# leo_joy_gamer_v2.net
KiCad netlist of a schematic drawn in EAGLE
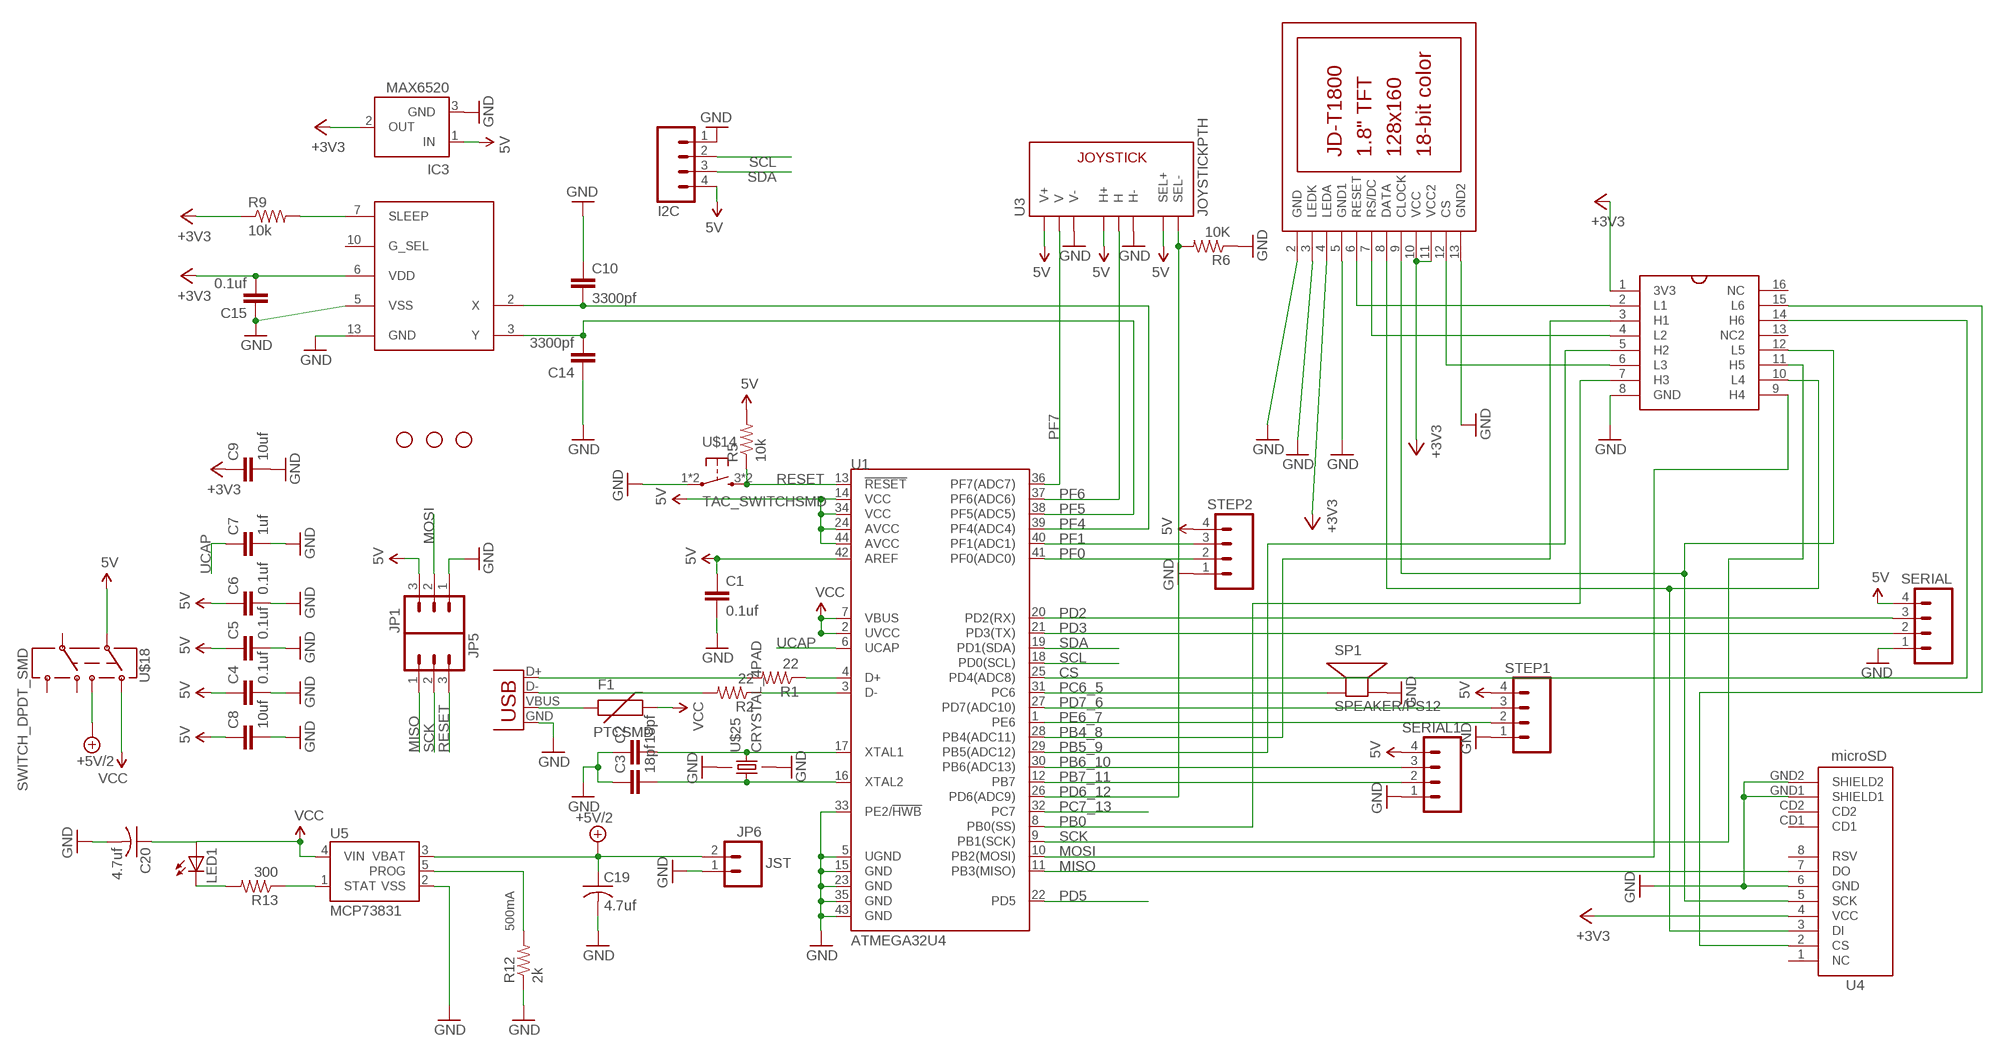
[diagram p0: schematic, sheet 1]

(export (version "E")
  (design (tool "Eeschema 10.0.6"))
  (components
    (comp (ref "C1")
      (value "0.1uf")
      (footprint "eagle-import:0805")
      (libsource (lib "eagle-import") (part "CAP0805"))
    )
    (comp (ref "C2")
      (value "18pf")
      (footprint "eagle-import:0805")
      (libsource (lib "eagle-import") (part "CAP0805"))
    )
    (comp (ref "C3")
      (value "18pf")
      (footprint "eagle-import:0805")
      (libsource (lib "eagle-import") (part "CAP0805"))
    )
    (comp (ref "C4")
      (value "0.1uf")
      (footprint "eagle-import:0805")
      (libsource (lib "eagle-import") (part "CAP0805"))
    )
    (comp (ref "C5")
      (value "0.1uf")
      (footprint "eagle-import:0805")
      (libsource (lib "eagle-import") (part "CAP0805"))
    )
    (comp (ref "C6")
      (value "0.1uf")
      (footprint "eagle-import:0805")
      (libsource (lib "eagle-import") (part "CAP0805"))
    )
    (comp (ref "C7")
      (value "1uf")
      (footprint "eagle-import:0805")
      (libsource (lib "eagle-import") (part "CAP0805"))
    )
    (comp (ref "C8")
      (value "10uf")
      (footprint "eagle-import:0805")
      (libsource (lib "eagle-import") (part "CAP0805"))
    )
    (comp (ref "C9")
      (value "10uf")
      (footprint "eagle-import:0805")
      (libsource (lib "eagle-import") (part "CAP0805"))
    )
    (comp (ref "C10")
      (value "3300pf")
      (footprint "eagle-import:0805")
      (libsource (lib "eagle-import") (part "CAP0805"))
    )
    (comp (ref "C14")
      (value "3300pf")
      (footprint "eagle-import:0805")
      (libsource (lib "eagle-import") (part "CAP0805"))
    )
    (comp (ref "C15")
      (value "0.1uf")
      (footprint "eagle-import:0805")
      (libsource (lib "eagle-import") (part "CAP0805"))
    )
    (comp (ref "C19")
      (value "4.7uf")
      (footprint "eagle-import:C0603")
      (libsource (lib "eagle-import") (part "C-USC0603"))
    )
    (comp (ref "C20")
      (value "4.7uf")
      (footprint "eagle-import:C0603")
      (libsource (lib "eagle-import") (part "C-USC0603"))
    )
    (comp (ref "F1")
      (value "PTCSMD")
      (footprint "eagle-import:PTC-1206")
      (libsource (lib "eagle-import") (part "PTCSMD"))
    )
    (comp (ref "I2C")
      (value "M04LOCK")
      (footprint "eagle-import:1X04_LOCK")
      (libsource (lib "eagle-import") (part "M04LOCK"))
    )
    (comp (ref "IC3")
      (value "MAX6520")
      (footprint "eagle-import:SOT23")
      (libsource (lib "eagle-import") (part "MAX6520"))
    )
    (comp (ref "JP1")
      (value "M03LOCK")
      (footprint "eagle-import:1X03_LOCK")
      (libsource (lib "eagle-import") (part "M03LOCK"))
    )
    (comp (ref "JP2")
      (value "STAND-OFF")
      (footprint "eagle-import:STAND-OFF")
      (libsource (lib "eagle-import") (part "STAND-OFF"))
    )
    (comp (ref "JP3")
      (value "STAND-OFF")
      (footprint "eagle-import:STAND-OFF")
      (libsource (lib "eagle-import") (part "STAND-OFF"))
    )
    (comp (ref "JP4")
      (value "STAND-OFF")
      (footprint "eagle-import:STAND-OFF")
      (libsource (lib "eagle-import") (part "STAND-OFF"))
    )
    (comp (ref "JP5")
      (value "M03LOCK")
      (footprint "eagle-import:1X03_LOCK")
      (libsource (lib "eagle-import") (part "M03LOCK"))
    )
    (comp (ref "JP6")
      (value "JST")
      (footprint "eagle-import:JST-2-PTH")
      (libsource (lib "eagle-import") (part "M02JST-PTH-2"))
    )
    (comp (ref "LCD1")
      (value "JD-T1800")
      (footprint "eagle-import:JD-T1800")
      (libsource (lib "eagle-import") (part "JD-T1800"))
    )
    (comp (ref "LED1")
      (value "LEDCHIPLED_1206")
      (footprint "eagle-import:CHIPLED_1206")
      (libsource (lib "eagle-import") (part "LEDCHIPLED_1206"))
    )
    (comp (ref "R1")
      (value "22")
      (footprint "eagle-import:M0805")
      (libsource (lib "eagle-import") (part "R-US_M0805"))
    )
    (comp (ref "R2")
      (value "22")
      (footprint "eagle-import:M0805")
      (libsource (lib "eagle-import") (part "R-US_M0805"))
    )
    (comp (ref "R5")
      (value "10k")
      (footprint "eagle-import:M0805")
      (libsource (lib "eagle-import") (part "R-US_M0805"))
    )
    (comp (ref "R6")
      (value "10K")
      (footprint "eagle-import:R0603")
      (libsource (lib "eagle-import") (part "R-US_R0603"))
    )
    (comp (ref "R9")
      (value "10k")
      (footprint "eagle-import:R0805")
      (libsource (lib "eagle-import") (part "R-US_R0805"))
    )
    (comp (ref "R12")
      (value "2k")
      (footprint "eagle-import:R0805")
      (libsource (lib "eagle-import") (part "R-US_R0805"))
    )
    (comp (ref "R13")
      (value "300")
      (footprint "eagle-import:R0805")
      (libsource (lib "eagle-import") (part "R-US_R0805"))
    )
    (comp (ref "SERIAL")
      (value "M04LOCK")
      (footprint "eagle-import:1X04_LOCK")
      (libsource (lib "eagle-import") (part "M04LOCK"))
    )
    (comp (ref "SERIAL1")
      (value "M04LOCK")
      (footprint "eagle-import:1X04_LOCK")
      (libsource (lib "eagle-import") (part "M04LOCK"))
    )
    (comp (ref "SP1")
      (value "SPEAKER/PS12")
      (footprint "eagle-import:PS12")
      (libsource (lib "eagle-import") (part "SPEAKER/PS12"))
    )
    (comp (ref "STEP1")
      (value "M04LOCK")
      (footprint "eagle-import:1X04_LOCK")
      (libsource (lib "eagle-import") (part "M04LOCK"))
    )
    (comp (ref "STEP2")
      (value "M04LOCK")
      (footprint "eagle-import:1X04_LOCK")
      (libsource (lib "eagle-import") (part "M04LOCK"))
    )
    (comp (ref "U$2")
      (value "CD4050SO_16_MIDDLE")
      (footprint "eagle-import:SO_16")
      (libsource (lib "eagle-import") (part "CD4050SO_16_MIDDLE"))
    )
    (comp (ref "U$12")
      (value "ACCELEROMETER_MMA6331L")
      (footprint "eagle-import:LGA14")
      (libsource (lib "eagle-import") (part "ACCELEROMETER_MMA6331L"))
    )
    (comp (ref "U$14")
      (value "TAC_SWITCHSMD")
      (footprint "eagle-import:TAC_SWITCH_SMD")
      (libsource (lib "eagle-import") (part "TAC_SWITCHSMD"))
    )
    (comp (ref "U$18")
      (value "SWITCH_DPDT_SMD")
      (footprint "eagle-import:SWITCH_DPDT")
      (libsource (lib "eagle-import") (part "SWITCH_DPDT_SMD"))
    )
    (comp (ref "U$25")
      (value "CRYSTAL_4PAD")
      (footprint "eagle-import:CRYSTAL_4PAD_TINY")
      (libsource (lib "eagle-import") (part "CRYSTAL_4PAD"))
    )
    (comp (ref "U1")
      (value "ATMEGA32U4")
      (footprint "eagle-import:QFN-44-NOPAD")
      (libsource (lib "eagle-import") (part "ATMEGA32U4QFN2"))
    )
    (comp (ref "U3")
      (value "JOYSTICKPTH")
      (footprint "eagle-import:JOYSTICK")
      (libsource (lib "eagle-import") (part "JOYSTICKPTH"))
    )
    (comp (ref "U4")
      (value "microSD")
      (footprint "eagle-import:MICRO-SD-SOCKET-PP")
      (libsource (lib "eagle-import") (part "USD-SOCKETSMD"))
    )
    (comp (ref "U5")
      (value "MCP73831")
      (footprint "eagle-import:SOT23-5")
      (libsource (lib "eagle-import") (part "MCP73831"))
    )
    (comp (ref "X1")
      (value "USBSMD")
      (footprint "eagle-import:USB-MINIB")
      (libsource (lib "eagle-import") (part "USBSMD"))
    )
  )
  (nets
    (net (code "1") (name "+3V3") (class "Default")
      (node (ref "C15") (pin "2") (pinfunction "2_2") (pintype "passive"))
      (node (ref "C9") (pin "1") (pinfunction "1_1") (pintype "passive"))
      (node (ref "IC3") (pin "2") (pinfunction "OUT_2") (pintype "input"))
      (node (ref "LCD1") (pin "10") (pinfunction "VCC_10") (pintype "power_in"))
      (node (ref "LCD1") (pin "11") (pinfunction "VCC2_11") (pintype "power_in"))
      (node (ref "LCD1") (pin "4") (pinfunction "LEDA_4") (pintype "input"))
      (node (ref "R9") (pin "1") (pinfunction "1_1") (pintype "passive"))
      (node (ref "U$12") (pin "6") (pinfunction "VDD_6") (pintype "bidirectional"))
      (node (ref "U$2") (pin "1") (pinfunction "3V3_1") (pintype "bidirectional"))
      (node (ref "U4") (pin "4") (pinfunction "VCC_4") (pintype "bidirectional"))
    )
    (net (code "2") (name "+5V{slash}2") (class "Default")
      (node (ref "C19") (pin "1") (pinfunction "1_1") (pintype "passive"))
      (node (ref "JP6") (pin "2") (pinfunction "2_2") (pintype "passive"))
      (node (ref "U$18") (pin "8") (pinfunction "3_8") (pintype "bidirectional"))
      (node (ref "U5") (pin "3") (pinfunction "VBAT_3") (pintype "power_in"))
    )
    (net (code "3") (name "/CS") (class "Default")
      (node (ref "U$2") (pin "14") (pinfunction "H6_14") (pintype "bidirectional"))
      (node (ref "U1") (pin "25") (pinfunction "PD4(ADC8)_25") (pintype "bidirectional"))
    )
    (net (code "4") (name "/MISO") (class "Default")
      (node (ref "JP5") (pin "1") (pinfunction "1_1") (pintype "passive"))
      (node (ref "U1") (pin "11") (pinfunction "PB3(MISO)_11") (pintype "bidirectional"))
      (node (ref "U4") (pin "7") (pinfunction "DO_7") (pintype "bidirectional"))
    )
    (net (code "5") (name "/MOSI") (class "Default")
      (node (ref "JP1") (pin "2") (pinfunction "2_2") (pintype "passive"))
      (node (ref "U$2") (pin "9") (pinfunction "H4_9") (pintype "bidirectional"))
      (node (ref "U1") (pin "10") (pinfunction "PB2(MOSI)_10") (pintype "bidirectional"))
    )
    (net (code "6") (name "/PB0") (class "Default")
      (node (ref "U$2") (pin "7") (pinfunction "H3_7") (pintype "bidirectional"))
      (node (ref "U1") (pin "8") (pinfunction "PB0(SS)_8") (pintype "bidirectional"))
    )
    (net (code "7") (name "/PB4_8") (class "Default")
      (node (ref "U$2") (pin "3") (pinfunction "H1_3") (pintype "bidirectional"))
      (node (ref "U1") (pin "28") (pinfunction "PB4(ADC11)_28") (pintype "bidirectional"))
    )
    (net (code "8") (name "/PB5_9") (class "Default")
      (node (ref "U$2") (pin "5") (pinfunction "H2_5") (pintype "bidirectional"))
      (node (ref "U1") (pin "29") (pinfunction "PB5(ADC12)_29") (pintype "bidirectional"))
    )
    (net (code "9") (name "/PB6_10") (class "Default")
      (node (ref "SERIAL1") (pin "3") (pinfunction "3_3") (pintype "passive"))
      (node (ref "U1") (pin "30") (pinfunction "PB6(ADC13)_30") (pintype "bidirectional"))
    )
    (net (code "10") (name "/PB7_11") (class "Default")
      (node (ref "SERIAL1") (pin "2") (pinfunction "2_2") (pintype "passive"))
      (node (ref "U1") (pin "12") (pinfunction "PB7_12") (pintype "bidirectional"))
    )
    (net (code "11") (name "/PC6_5") (class "Default")
      (node (ref "SP1") (pin "P$1") (pinfunction "+_P$1") (pintype "passive"))
      (node (ref "U1") (pin "31") (pinfunction "PC6_31") (pintype "bidirectional"))
    )
    (net (code "12") (name "/PC7_13") (class "Default")
      (node (ref "U1") (pin "32") (pinfunction "PC7_32") (pintype "bidirectional"))
    )
    (net (code "13") (name "/PD2") (class "Default")
      (node (ref "SERIAL") (pin "3") (pinfunction "3_3") (pintype "passive"))
      (node (ref "U1") (pin "20") (pinfunction "PD2(RX)_20") (pintype "bidirectional"))
    )
    (net (code "14") (name "/PD3") (class "Default")
      (node (ref "SERIAL") (pin "2") (pinfunction "2_2") (pintype "passive"))
      (node (ref "U1") (pin "21") (pinfunction "PD3(TX)_21") (pintype "bidirectional"))
    )
    (net (code "15") (name "/PD5") (class "Default")
      (node (ref "U1") (pin "22") (pinfunction "PD5_22") (pintype "bidirectional"))
    )
    (net (code "16") (name "/PD6_12") (class "Default")
      (node (ref "R6") (pin "2") (pinfunction "2_2") (pintype "passive"))
      (node (ref "U1") (pin "26") (pinfunction "PD6(ADC9)_26") (pintype "bidirectional"))
      (node (ref "U3") (pin "B2A") (pinfunction "SEL-_B2A") (pintype "bidirectional"))
    )
    (net (code "17") (name "/PD7_6") (class "Default")
      (node (ref "STEP1") (pin "3") (pinfunction "3_3") (pintype "passive"))
      (node (ref "U1") (pin "27") (pinfunction "PD7(ADC10)_27") (pintype "bidirectional"))
    )
    (net (code "18") (name "/PE6_7") (class "Default")
      (node (ref "STEP1") (pin "2") (pinfunction "2_2") (pintype "passive"))
      (node (ref "U1") (pin "1") (pinfunction "PE6_1") (pintype "bidirectional"))
    )
    (net (code "19") (name "/PF0") (class "Default")
      (node (ref "STEP2") (pin "2") (pinfunction "2_2") (pintype "passive"))
      (node (ref "U1") (pin "41") (pinfunction "PF0(ADC0)_41") (pintype "bidirectional"))
    )
    (net (code "20") (name "/PF1") (class "Default")
      (node (ref "STEP2") (pin "3") (pinfunction "3_3") (pintype "passive"))
      (node (ref "U1") (pin "40") (pinfunction "PF1(ADC1)_40") (pintype "bidirectional"))
    )
    (net (code "21") (name "/PF4") (class "Default")
      (node (ref "C10") (pin "2") (pinfunction "2_2") (pintype "passive"))
      (node (ref "U$12") (pin "2") (pinfunction "X_2") (pintype "bidirectional"))
      (node (ref "U1") (pin "39") (pinfunction "PF4(ADC4)_39") (pintype "bidirectional"))
    )
    (net (code "22") (name "/PF5") (class "Default")
      (node (ref "C14") (pin "2") (pinfunction "2_2") (pintype "passive"))
      (node (ref "U$12") (pin "3") (pinfunction "Y_3") (pintype "bidirectional"))
      (node (ref "U1") (pin "38") (pinfunction "PF5(ADC5)_38") (pintype "bidirectional"))
    )
    (net (code "23") (name "/PF6") (class "Default")
      (node (ref "U1") (pin "37") (pinfunction "PF6(ADC6)_37") (pintype "bidirectional"))
      (node (ref "U3") (pin "H2") (pinfunction "H_H2") (pintype "bidirectional"))
    )
    (net (code "24") (name "/PF7") (class "Default")
      (node (ref "U1") (pin "36") (pinfunction "PF7(ADC7)_36") (pintype "bidirectional"))
      (node (ref "U3") (pin "V2") (pinfunction "V_V2") (pintype "bidirectional"))
    )
    (net (code "25") (name "/RESET") (class "Default")
      (node (ref "JP5") (pin "3") (pinfunction "3_3") (pintype "passive"))
      (node (ref "R5") (pin "1") (pinfunction "1_1") (pintype "passive"))
      (node (ref "U$14") (pin "3") (pinfunction "3_3") (pintype "passive"))
      (node (ref "U$14") (pin "4") (pinfunction "3_4") (pintype "passive"))
      (node (ref "U1") (pin "13") (pinfunction "~{RESET}_13") (pintype "bidirectional"))
    )
    (net (code "26") (name "/SCK") (class "Default")
      (node (ref "JP5") (pin "2") (pinfunction "2_2") (pintype "passive"))
      (node (ref "U$2") (pin "11") (pinfunction "H5_11") (pintype "bidirectional"))
      (node (ref "U1") (pin "9") (pinfunction "PB1(SCK)_9") (pintype "bidirectional"))
    )
    (net (code "27") (name "/SCL") (class "Default")
      (node (ref "I2C") (pin "2") (pinfunction "2_2") (pintype "passive"))
      (node (ref "U1") (pin "18") (pinfunction "PD0(SCL)_18") (pintype "bidirectional"))
    )
    (net (code "28") (name "/SDA") (class "Default")
      (node (ref "I2C") (pin "3") (pinfunction "3_3") (pintype "passive"))
      (node (ref "U1") (pin "19") (pinfunction "PD1(SDA)_19") (pintype "bidirectional"))
    )
    (net (code "29") (name "/UCAP") (class "Default")
      (node (ref "C7") (pin "1") (pinfunction "1_1") (pintype "passive"))
      (node (ref "U1") (pin "6") (pinfunction "UCAP_6") (pintype "bidirectional"))
    )
    (net (code "30") (name "5V") (class "Default")
      (node (ref "C1") (pin "1") (pinfunction "1_1") (pintype "passive"))
      (node (ref "C4") (pin "1") (pinfunction "1_1") (pintype "passive"))
      (node (ref "C5") (pin "1") (pinfunction "1_1") (pintype "passive"))
      (node (ref "C6") (pin "1") (pinfunction "1_1") (pintype "passive"))
      (node (ref "C8") (pin "1") (pinfunction "1_1") (pintype "passive"))
      (node (ref "I2C") (pin "4") (pinfunction "4_4") (pintype "passive"))
      (node (ref "IC3") (pin "1") (pinfunction "IN_1") (pintype "input"))
      (node (ref "JP1") (pin "3") (pinfunction "3_3") (pintype "passive"))
      (node (ref "R5") (pin "2") (pinfunction "2_2") (pintype "passive"))
      (node (ref "SERIAL") (pin "4") (pinfunction "4_4") (pintype "passive"))
      (node (ref "SERIAL1") (pin "4") (pinfunction "4_4") (pintype "passive"))
      (node (ref "STEP1") (pin "4") (pinfunction "4_4") (pintype "passive"))
      (node (ref "STEP2") (pin "4") (pinfunction "4_4") (pintype "passive"))
      (node (ref "U$18") (pin "7") (pinfunction "2_7") (pintype "bidirectional"))
      (node (ref "U1") (pin "14") (pinfunction "VCC_14") (pintype "bidirectional"))
      (node (ref "U1") (pin "24") (pinfunction "AVCC_24") (pintype "bidirectional"))
      (node (ref "U1") (pin "34") (pinfunction "VCC_34") (pintype "bidirectional"))
      (node (ref "U1") (pin "42") (pinfunction "AREF_42") (pintype "bidirectional"))
      (node (ref "U1") (pin "44") (pinfunction "AVCC_44") (pintype "bidirectional"))
      (node (ref "U3") (pin "B1A") (pinfunction "SEL+_B1A") (pintype "bidirectional"))
      (node (ref "U3") (pin "H1") (pinfunction "H+_H1") (pintype "bidirectional"))
      (node (ref "U3") (pin "V1") (pinfunction "V+_V1") (pintype "bidirectional"))
    )
    (net (code "31") (name "GND") (class "Default")
      (node (ref "C1") (pin "2") (pinfunction "2_2") (pintype "passive"))
      (node (ref "C10") (pin "1") (pinfunction "1_1") (pintype "passive"))
      (node (ref "C14") (pin "1") (pinfunction "1_1") (pintype "passive"))
      (node (ref "C15") (pin "1") (pinfunction "1_1") (pintype "passive"))
      (node (ref "C19") (pin "2") (pinfunction "2_2") (pintype "passive"))
      (node (ref "C2") (pin "1") (pinfunction "1_1") (pintype "passive"))
      (node (ref "C20") (pin "2") (pinfunction "2_2") (pintype "passive"))
      (node (ref "C3") (pin "1") (pinfunction "1_1") (pintype "passive"))
      (node (ref "C4") (pin "2") (pinfunction "2_2") (pintype "passive"))
      (node (ref "C5") (pin "2") (pinfunction "2_2") (pintype "passive"))
      (node (ref "C6") (pin "2") (pinfunction "2_2") (pintype "passive"))
      (node (ref "C7") (pin "2") (pinfunction "2_2") (pintype "passive"))
      (node (ref "C8") (pin "2") (pinfunction "2_2") (pintype "passive"))
      (node (ref "C9") (pin "2") (pinfunction "2_2") (pintype "passive"))
      (node (ref "I2C") (pin "1") (pinfunction "1_1") (pintype "passive"))
      (node (ref "IC3") (pin "3") (pinfunction "GND_3") (pintype "power_in"))
      (node (ref "JP1") (pin "1") (pinfunction "1_1") (pintype "passive"))
      (node (ref "JP6") (pin "1") (pinfunction "1_1") (pintype "passive"))
      (node (ref "LCD1") (pin "13") (pinfunction "GND2_13") (pintype "power_in"))
      (node (ref "LCD1") (pin "2") (pinfunction "GND_2") (pintype "power_in"))
      (node (ref "LCD1") (pin "3") (pinfunction "LEDK_3") (pintype "input"))
      (node (ref "LCD1") (pin "5") (pinfunction "GND1_5") (pintype "power_in"))
      (node (ref "R12") (pin "1") (pinfunction "1_1") (pintype "passive"))
      (node (ref "R6") (pin "1") (pinfunction "1_1") (pintype "passive"))
      (node (ref "SERIAL") (pin "1") (pinfunction "1_1") (pintype "passive"))
      (node (ref "SERIAL1") (pin "1") (pinfunction "1_1") (pintype "passive"))
      (node (ref "SP1") (pin "P$2") (pinfunction "-_P$2") (pintype "passive"))
      (node (ref "STEP1") (pin "1") (pinfunction "1_1") (pintype "passive"))
      (node (ref "STEP2") (pin "1") (pinfunction "1_1") (pintype "passive"))
      (node (ref "U$12") (pin "13") (pinfunction "GND_13") (pintype "bidirectional"))
      (node (ref "U$12") (pin "5") (pinfunction "VSS_5") (pintype "bidirectional"))
      (node (ref "U$14") (pin "1") (pinfunction "1_1") (pintype "passive"))
      (node (ref "U$14") (pin "2") (pinfunction "1_2") (pintype "passive"))
      (node (ref "U$2") (pin "8") (pinfunction "GND_8") (pintype "bidirectional"))
      (node (ref "U$25") (pin "2") (pinfunction "GND2_2") (pintype "bidirectional"))
      (node (ref "U$25") (pin "4") (pinfunction "GND4_4") (pintype "bidirectional"))
      (node (ref "U1") (pin "15") (pinfunction "GND_15") (pintype "bidirectional"))
      (node (ref "U1") (pin "23") (pinfunction "GND_23") (pintype "bidirectional"))
      (node (ref "U1") (pin "33") (pinfunction "PE2/~{HWB}_33") (pintype "bidirectional"))
      (node (ref "U1") (pin "35") (pinfunction "GND_35") (pintype "bidirectional"))
      (node (ref "U1") (pin "43") (pinfunction "GND_43") (pintype "bidirectional"))
      (node (ref "U1") (pin "5") (pinfunction "UGND_5") (pintype "bidirectional"))
      (node (ref "U3") (pin "H3") (pinfunction "H-_H3") (pintype "bidirectional"))
      (node (ref "U3") (pin "V3") (pinfunction "V-_V3") (pintype "bidirectional"))
      (node (ref "U4") (pin "6") (pinfunction "GND_6") (pintype "bidirectional"))
      (node (ref "U4") (pin "GND1") (pinfunction "SHIELD1_GND1") (pintype "bidirectional"))
      (node (ref "U4") (pin "GND2") (pinfunction "SHIELD2_GND2") (pintype "bidirectional"))
      (node (ref "U5") (pin "2") (pinfunction "VSS_2") (pintype "power_in"))
      (node (ref "X1") (pin "GND") (pinfunction "GND_GND") (pintype "bidirectional"))
    )
    (net (code "32") (name "Net-(F1-Pad1)") (class "Default")
      (node (ref "F1") (pin "1") (pinfunction "1_1") (pintype "bidirectional"))
      (node (ref "X1") (pin "VBUS") (pinfunction "VBUS_VBUS") (pintype "bidirectional"))
    )
    (net (code "33") (name "Net-(LCD1-CLOCK)") (class "Default")
      (node (ref "LCD1") (pin "9") (pinfunction "CLOCK_9") (pintype "input"))
      (node (ref "U$2") (pin "12") (pinfunction "L5_12") (pintype "bidirectional"))
      (node (ref "U4") (pin "5") (pinfunction "SCK_5") (pintype "bidirectional"))
    )
    (net (code "34") (name "Net-(LCD1-CS)") (class "Default")
      (node (ref "LCD1") (pin "12") (pinfunction "CS_12") (pintype "input"))
      (node (ref "U$2") (pin "6") (pinfunction "L3_6") (pintype "bidirectional"))
    )
    (net (code "35") (name "Net-(LCD1-DATA)") (class "Default")
      (node (ref "LCD1") (pin "8") (pinfunction "DATA_8") (pintype "bidirectional"))
      (node (ref "U$2") (pin "10") (pinfunction "L4_10") (pintype "bidirectional"))
      (node (ref "U4") (pin "3") (pinfunction "DI_3") (pintype "bidirectional"))
    )
    (net (code "36") (name "Net-(LCD1-RESET)") (class "Default")
      (node (ref "LCD1") (pin "6") (pinfunction "RESET_6") (pintype "input"))
      (node (ref "U$2") (pin "2") (pinfunction "L1_2") (pintype "bidirectional"))
    )
    (net (code "37") (name "Net-(LCD1-RS{slash}DC)") (class "Default")
      (node (ref "LCD1") (pin "7") (pinfunction "RS/DC_7") (pintype "input"))
      (node (ref "U$2") (pin "4") (pinfunction "L2_4") (pintype "bidirectional"))
    )
    (net (code "38") (name "Net-(LED1-PadC)") (class "Default")
      (node (ref "LED1") (pin "C") (pinfunction "C_C") (pintype "passive"))
      (node (ref "R13") (pin "2") (pinfunction "2_2") (pintype "passive"))
    )
    (net (code "39") (name "Net-(R1-Pad2)") (class "Default")
      (node (ref "R1") (pin "2") (pinfunction "2_2") (pintype "passive"))
      (node (ref "X1") (pin "D+") (pinfunction "D+_D+") (pintype "bidirectional"))
    )
    (net (code "40") (name "Net-(R2-Pad2)") (class "Default")
      (node (ref "R2") (pin "2") (pinfunction "2_2") (pintype "passive"))
      (node (ref "X1") (pin "D-") (pinfunction "D-_D-") (pintype "bidirectional"))
    )
    (net (code "41") (name "Net-(U$2-L6)") (class "Default")
      (node (ref "U$2") (pin "15") (pinfunction "L6_15") (pintype "bidirectional"))
      (node (ref "U4") (pin "2") (pinfunction "CS_2") (pintype "bidirectional"))
    )
    (net (code "42") (name "Net-(U$12-SLEEP)") (class "Default")
      (node (ref "R9") (pin "2") (pinfunction "2_2") (pintype "passive"))
      (node (ref "U$12") (pin "7") (pinfunction "SLEEP_7") (pintype "bidirectional"))
    )
    (net (code "43") (name "Net-(U1-D+)") (class "Default")
      (node (ref "R1") (pin "1") (pinfunction "1_1") (pintype "passive"))
      (node (ref "U1") (pin "4") (pinfunction "D+_4") (pintype "bidirectional"))
    )
    (net (code "44") (name "Net-(U1-D-)") (class "Default")
      (node (ref "R2") (pin "1") (pinfunction "1_1") (pintype "passive"))
      (node (ref "U1") (pin "3") (pinfunction "D-_3") (pintype "bidirectional"))
    )
    (net (code "45") (name "Net-(U1-XTAL1)") (class "Default")
      (node (ref "C2") (pin "2") (pinfunction "2_2") (pintype "passive"))
      (node (ref "U$25") (pin "3") (pinfunction "3_3") (pintype "passive"))
      (node (ref "U1") (pin "17") (pinfunction "XTAL1_17") (pintype "bidirectional"))
    )
    (net (code "46") (name "Net-(U1-XTAL2)") (class "Default")
      (node (ref "C3") (pin "2") (pinfunction "2_2") (pintype "passive"))
      (node (ref "U$25") (pin "1") (pinfunction "1_1") (pintype "passive"))
      (node (ref "U1") (pin "16") (pinfunction "XTAL2_16") (pintype "bidirectional"))
    )
    (net (code "47") (name "Net-(U5-PROG)") (class "Default")
      (node (ref "R12") (pin "2") (pinfunction "2_2") (pintype "passive"))
      (node (ref "U5") (pin "5") (pinfunction "PROG_5") (pintype "input"))
    )
    (net (code "48") (name "Net-(U5-STAT)") (class "Default")
      (node (ref "R13") (pin "1") (pinfunction "1_1") (pintype "passive"))
      (node (ref "U5") (pin "1") (pinfunction "STAT_1") (pintype "output"))
    )
    (net (code "49") (name "VCC") (class "Default")
      (node (ref "C20") (pin "1") (pinfunction "1_1") (pintype "passive"))
      (node (ref "F1") (pin "2") (pinfunction "2_2") (pintype "bidirectional"))
      (node (ref "LED1") (pin "A") (pinfunction "A_A") (pintype "passive"))
      (node (ref "U$18") (pin "1") (pinfunction "1_1") (pintype "bidirectional"))
      (node (ref "U1") (pin "2") (pinfunction "UVCC_2") (pintype "bidirectional"))
      (node (ref "U1") (pin "7") (pinfunction "VBUS_7") (pintype "bidirectional"))
      (node (ref "U5") (pin "4") (pinfunction "VIN_4") (pintype "power_in"))
    )
    (net (code "50") (name "unconnected-(U$2-NC-Pad16)") (class "Default")
      (node (ref "U$2") (pin "16") (pinfunction "NC_16") (pintype "bidirectional"))
    )
    (net (code "51") (name "unconnected-(U$2-NC2-Pad13)") (class "Default")
      (node (ref "U$2") (pin "13") (pinfunction "NC2_13") (pintype "bidirectional"))
    )
    (net (code "52") (name "unconnected-(U$12-G_SEL-Pad10)") (class "Default")
      (node (ref "U$12") (pin "10") (pinfunction "G_SEL_10") (pintype "bidirectional"))
    )
    (net (code "53") (name "unconnected-(U$18-4-Pad9)") (class "Default")
      (node (ref "U$18") (pin "9") (pinfunction "4_9") (pintype "bidirectional"))
    )
    (net (code "54") (name "unconnected-(U$18-5-Pad10)") (class "Default")
      (node (ref "U$18") (pin "10") (pinfunction "5_10") (pintype "bidirectional"))
    )
    (net (code "55") (name "unconnected-(U$18-6-Pad11)") (class "Default")
      (node (ref "U$18") (pin "11") (pinfunction "6_11") (pintype "bidirectional"))
    )
    (net (code "56") (name "unconnected-(U4-NC-Pad1)") (class "Default")
      (node (ref "U4") (pin "1") (pinfunction "NC_1") (pintype "bidirectional"))
    )
    (net (code "57") (name "unconnected-(U4-PadCD1)") (class "Default")
      (node (ref "U4") (pin "CD1") (pinfunction "CD1_CD1") (pintype "bidirectional"))
    )
    (net (code "58") (name "unconnected-(U4-PadCD2)") (class "Default")
      (node (ref "U4") (pin "CD2") (pinfunction "CD2_CD2") (pintype "bidirectional"))
    )
    (net (code "59") (name "unconnected-(U4-RSV-Pad8)") (class "Default")
      (node (ref "U4") (pin "8") (pinfunction "RSV_8") (pintype "bidirectional"))
    )
  )
)
